# led_matrix.net
KiCad netlist of a schematic drawn in EAGLE
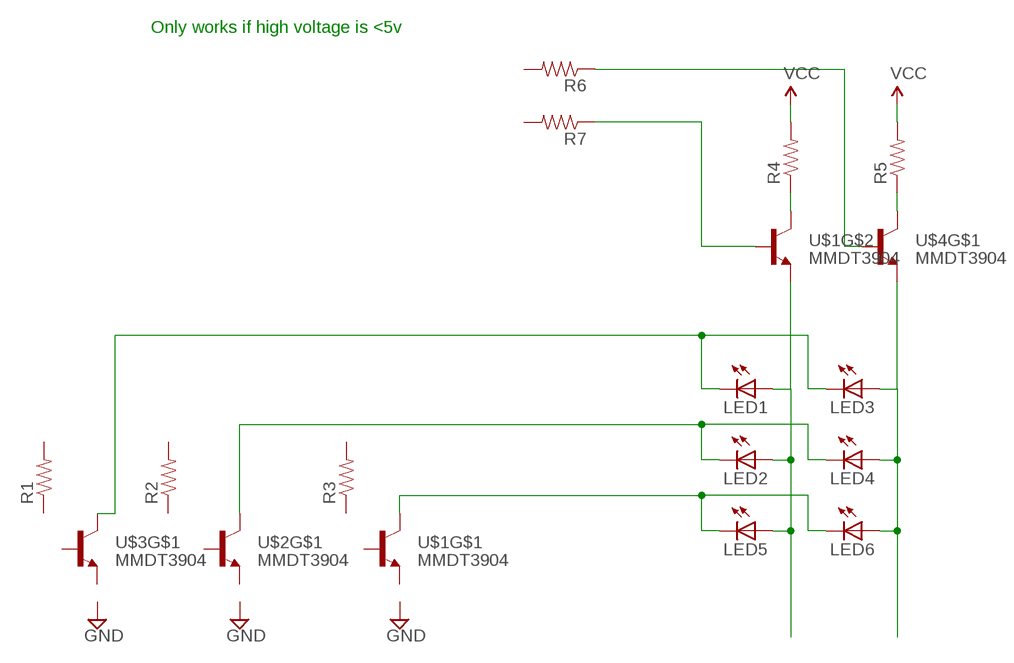
[diagram p0: schematic, sheet 1]

(export (version "E")
  (design (tool "Eeschema 10.0.6"))
  (components
    (comp (ref "LED1")
      (value "LED0805")
      (footprint "eagle-import:LED_0805")
      (libsource (lib "eagle-import") (part "LED0805"))
    )
    (comp (ref "LED2")
      (value "LED0805")
      (footprint "eagle-import:LED_0805")
      (libsource (lib "eagle-import") (part "LED0805"))
    )
    (comp (ref "LED3")
      (value "LED0805")
      (footprint "eagle-import:LED_0805")
      (libsource (lib "eagle-import") (part "LED0805"))
    )
    (comp (ref "LED4")
      (value "LED0805")
      (footprint "eagle-import:LED_0805")
      (libsource (lib "eagle-import") (part "LED0805"))
    )
    (comp (ref "LED5")
      (value "LED0805")
      (footprint "eagle-import:LED_0805")
      (libsource (lib "eagle-import") (part "LED0805"))
    )
    (comp (ref "LED6")
      (value "LED0805")
      (footprint "eagle-import:LED_0805")
      (libsource (lib "eagle-import") (part "LED0805"))
    )
    (comp (ref "R1")
      (value "RESISTOR0805-RES")
      (footprint "eagle-import:0805")
      (libsource (lib "eagle-import") (part "RESISTOR0805-RES"))
    )
    (comp (ref "R2")
      (value "RESISTOR0805-RES")
      (footprint "eagle-import:0805")
      (libsource (lib "eagle-import") (part "RESISTOR0805-RES"))
    )
    (comp (ref "R3")
      (value "RESISTOR0805-RES")
      (footprint "eagle-import:0805")
      (libsource (lib "eagle-import") (part "RESISTOR0805-RES"))
    )
    (comp (ref "R4")
      (value "RESISTOR0805-RES")
      (footprint "eagle-import:0805")
      (libsource (lib "eagle-import") (part "RESISTOR0805-RES"))
    )
    (comp (ref "R5")
      (value "RESISTOR0805-RES")
      (footprint "eagle-import:0805")
      (libsource (lib "eagle-import") (part "RESISTOR0805-RES"))
    )
    (comp (ref "R6")
      (value "RESISTOR0805-RES")
      (footprint "eagle-import:0805")
      (libsource (lib "eagle-import") (part "RESISTOR0805-RES"))
    )
    (comp (ref "R7")
      (value "RESISTOR0805-RES")
      (footprint "eagle-import:0805")
      (libsource (lib "eagle-import") (part "RESISTOR0805-RES"))
    )
    (comp (ref "U$1")
      (value "MMDT3904")
      (footprint "eagle-import:SOT363")
      (libsource (lib "eagle-import") (part "MMDT3904"))
    )
    (comp (ref "U$2")
      (value "MMDT3904")
      (footprint "eagle-import:SOT363")
      (libsource (lib "eagle-import") (part "MMDT3904"))
    )
    (comp (ref "U$3")
      (value "MMDT3904")
      (footprint "eagle-import:SOT363")
      (libsource (lib "eagle-import") (part "MMDT3904"))
    )
    (comp (ref "U$4")
      (value "MMDT3904")
      (footprint "eagle-import:SOT363")
      (libsource (lib "eagle-import") (part "MMDT3904"))
    )
  )
  (nets
    (net (code "2") (name "Net-(U$1A-C)") (class "Default")
      (node (ref "LED5") (pin "C") (pinfunction "C_C") (pintype "passive"))
      (node (ref "LED6") (pin "C") (pinfunction "C_C") (pintype "passive"))
      (node (ref "U$1") (pin "3") (pinfunction "C_3") (pintype "passive"))
    )
    (net (code "3") (name "Net-(U$1B-B)") (class "Default")
      (node (ref "R7") (pin "1") (pinfunction "1_1") (pintype "passive"))
      (node (ref "U$1") (pin "2") (pinfunction "B_2") (pintype "passive"))
    )
    (net (code "4") (name "Net-(U$1B-C)") (class "Default")
      (node (ref "R4") (pin "1") (pinfunction "1_1") (pintype "passive"))
      (node (ref "U$1") (pin "6") (pinfunction "C_6") (pintype "passive"))
    )
    (net (code "5") (name "Net-(U$1B-E)") (class "Default")
      (node (ref "LED1") (pin "A") (pinfunction "A_A") (pintype "passive"))
      (node (ref "LED2") (pin "A") (pinfunction "A_A") (pintype "passive"))
      (node (ref "LED5") (pin "A") (pinfunction "A_A") (pintype "passive"))
      (node (ref "U$1") (pin "1") (pinfunction "E_1") (pintype "passive"))
    )
    (net (code "6") (name "Net-(U$2A-C)") (class "Default")
      (node (ref "LED2") (pin "C") (pinfunction "C_C") (pintype "passive"))
      (node (ref "LED4") (pin "C") (pinfunction "C_C") (pintype "passive"))
      (node (ref "U$2") (pin "3") (pinfunction "C_3") (pintype "passive"))
    )
    (net (code "7") (name "Net-(U$3A-C)") (class "Default")
      (node (ref "LED1") (pin "C") (pinfunction "C_C") (pintype "passive"))
      (node (ref "LED3") (pin "C") (pinfunction "C_C") (pintype "passive"))
      (node (ref "U$3") (pin "3") (pinfunction "C_3") (pintype "passive"))
    )
    (net (code "8") (name "Net-(U$4A-B)") (class "Default")
      (node (ref "R6") (pin "1") (pinfunction "1_1") (pintype "passive"))
      (node (ref "U$4") (pin "5") (pinfunction "B_5") (pintype "passive"))
    )
    (net (code "9") (name "Net-(U$4A-C)") (class "Default")
      (node (ref "R5") (pin "1") (pinfunction "1_1") (pintype "passive"))
      (node (ref "U$4") (pin "3") (pinfunction "C_3") (pintype "passive"))
    )
    (net (code "10") (name "Net-(U$4A-E)") (class "Default")
      (node (ref "LED3") (pin "A") (pinfunction "A_A") (pintype "passive"))
      (node (ref "LED4") (pin "A") (pinfunction "A_A") (pintype "passive"))
      (node (ref "LED6") (pin "A") (pinfunction "A_A") (pintype "passive"))
      (node (ref "U$4") (pin "4") (pinfunction "E_4") (pintype "passive"))
    )
    (net (code "11") (name "VCC") (class "Default")
      (node (ref "R4") (pin "2") (pinfunction "2_2") (pintype "passive"))
      (node (ref "R5") (pin "2") (pinfunction "2_2") (pintype "passive"))
    )
    (net (code "12") (name "unconnected-(R1-Pad1)") (class "Default")
      (node (ref "R1") (pin "1") (pinfunction "1_1") (pintype "passive"))
    )
    (net (code "13") (name "unconnected-(R1-Pad2)") (class "Default")
      (node (ref "R1") (pin "2") (pinfunction "2_2") (pintype "passive"))
    )
    (net (code "14") (name "unconnected-(R2-Pad1)") (class "Default")
      (node (ref "R2") (pin "1") (pinfunction "1_1") (pintype "passive"))
    )
    (net (code "15") (name "unconnected-(R2-Pad2)") (class "Default")
      (node (ref "R2") (pin "2") (pinfunction "2_2") (pintype "passive"))
    )
    (net (code "16") (name "unconnected-(R3-Pad1)") (class "Default")
      (node (ref "R3") (pin "1") (pinfunction "1_1") (pintype "passive"))
    )
    (net (code "17") (name "unconnected-(R3-Pad2)") (class "Default")
      (node (ref "R3") (pin "2") (pinfunction "2_2") (pintype "passive"))
    )
    (net (code "18") (name "unconnected-(R6-Pad2)") (class "Default")
      (node (ref "R6") (pin "2") (pinfunction "2_2") (pintype "passive"))
    )
    (net (code "19") (name "unconnected-(R7-Pad2)") (class "Default")
      (node (ref "R7") (pin "2") (pinfunction "2_2") (pintype "passive"))
    )
    (net (code "20") (name "unconnected-(U$1A-B-Pad5)") (class "Default")
      (node (ref "U$1") (pin "5") (pinfunction "B_5") (pintype "passive"))
    )
    (net (code "21") (name "unconnected-(U$1A-E-Pad4)") (class "Default")
      (node (ref "U$1") (pin "4") (pinfunction "E_4") (pintype "passive"))
    )
    (net (code "22") (name "unconnected-(U$2A-B-Pad5)") (class "Default")
      (node (ref "U$2") (pin "5") (pinfunction "B_5") (pintype "passive"))
    )
    (net (code "23") (name "unconnected-(U$2A-E-Pad4)") (class "Default")
      (node (ref "U$2") (pin "4") (pinfunction "E_4") (pintype "passive"))
    )
    (net (code "24") (name "unconnected-(U$3A-B-Pad5)") (class "Default")
      (node (ref "U$3") (pin "5") (pinfunction "B_5") (pintype "passive"))
    )
    (net (code "25") (name "unconnected-(U$3A-E-Pad4)") (class "Default")
      (node (ref "U$3") (pin "4") (pinfunction "E_4") (pintype "passive"))
    )
  )
)
